# UV_MONITOR_V2_1.net
KiCad netlist of a schematic drawn in EAGLE
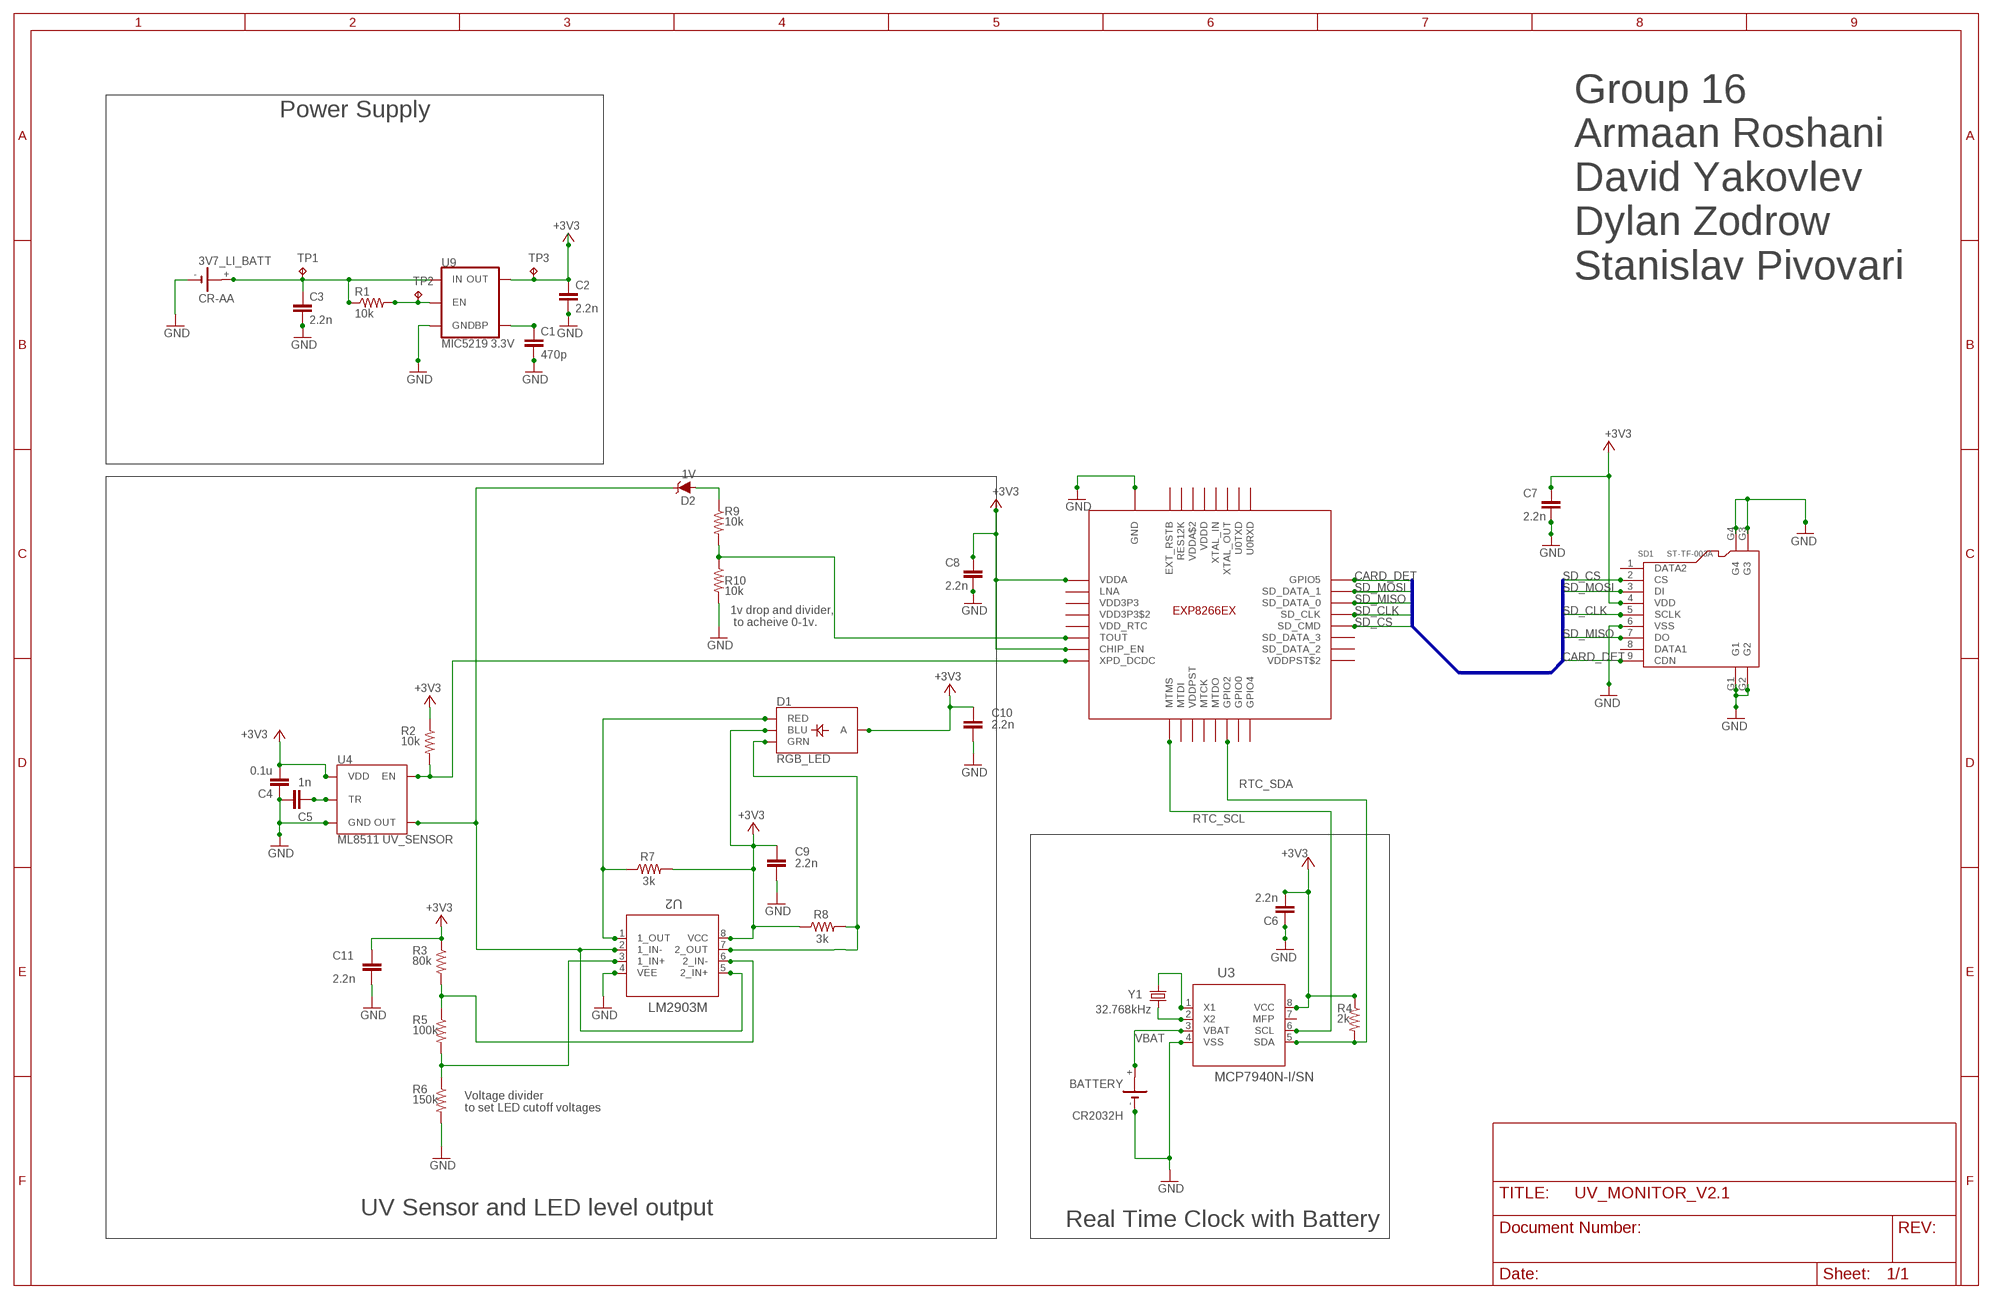
[diagram p0: schematic, sheet 1]

(export (version "E")
  (design (tool "Eeschema 10.0.6"))
  (components
    (comp (ref "3V7_LI_BATT")
      (value "CR-AA")
      (footprint "eagle-import:CRAA")
      (libsource (lib "eagle-import") (part "CR-AA"))
    )
    (comp (ref "BATTERY")
      (value "CR2032H")
      (footprint "eagle-import:CR2032H")
      (libsource (lib "eagle-import") (part "CR2032H"))
    )
    (comp (ref "C1")
      (value "470p")
      (footprint "eagle-import:C0805")
      (libsource (lib "eagle-import") (part "C-EUC0805"))
    )
    (comp (ref "C2")
      (value "2.2n")
      (footprint "eagle-import:C0805")
      (libsource (lib "eagle-import") (part "C-EUC0805"))
    )
    (comp (ref "C3")
      (value "2.2n")
      (footprint "eagle-import:C0805")
      (libsource (lib "eagle-import") (part "C-EUC0805"))
    )
    (comp (ref "C4")
      (value "0.1u")
      (footprint "eagle-import:C0805")
      (libsource (lib "eagle-import") (part "C-EUC0805"))
    )
    (comp (ref "C5")
      (value "1n")
      (footprint "eagle-import:C0805")
      (libsource (lib "eagle-import") (part "C-EUC0805"))
    )
    (comp (ref "C6")
      (value "2.2n")
      (footprint "eagle-import:C0805")
      (libsource (lib "eagle-import") (part "C-EUC0805"))
    )
    (comp (ref "C7")
      (value "2.2n")
      (footprint "eagle-import:C0805")
      (libsource (lib "eagle-import") (part "C-EUC0805"))
    )
    (comp (ref "C8")
      (value "2.2n")
      (footprint "eagle-import:C0805")
      (libsource (lib "eagle-import") (part "C-EUC0805"))
    )
    (comp (ref "C9")
      (value "2.2n")
      (footprint "eagle-import:C0805")
      (libsource (lib "eagle-import") (part "C-EUC0805"))
    )
    (comp (ref "C10")
      (value "2.2n")
      (footprint "eagle-import:C0805")
      (libsource (lib "eagle-import") (part "C-EUC0805"))
    )
    (comp (ref "C11")
      (value "2.2n")
      (footprint "eagle-import:C0805")
      (libsource (lib "eagle-import") (part "C-EUC0805"))
    )
    (comp (ref "D1")
      (value "RGB_LED")
      (footprint "eagle-import:LED-TRICOLOR-SMD")
      (libsource (lib "eagle-import") (part "LED-RGB-CASMD"))
    )
    (comp (ref "D2")
      (value "1V")
      (footprint "eagle-import:SOD-323")
      (libsource (lib "eagle-import") (part "DIODE-ZENER-BZT52C3V6S"))
    )
    (comp (ref "R1")
      (value "10k")
      (footprint "eagle-import:R0805")
      (libsource (lib "eagle-import") (part "R-US_R0805"))
    )
    (comp (ref "R2")
      (value "10k")
      (footprint "eagle-import:R0805")
      (libsource (lib "eagle-import") (part "R-US_R0805"))
    )
    (comp (ref "R3")
      (value "80k")
      (footprint "eagle-import:R0805")
      (libsource (lib "eagle-import") (part "R-US_R0805"))
    )
    (comp (ref "R4")
      (value "2k")
      (footprint "eagle-import:R0805")
      (libsource (lib "eagle-import") (part "R-US_R0805"))
    )
    (comp (ref "R5")
      (value "100k")
      (footprint "eagle-import:R0805")
      (libsource (lib "eagle-import") (part "R-US_R0805"))
    )
    (comp (ref "R6")
      (value "150k")
      (footprint "eagle-import:R0805")
      (libsource (lib "eagle-import") (part "R-US_R0805"))
    )
    (comp (ref "R7")
      (value "3k")
      (footprint "eagle-import:R0805")
      (libsource (lib "eagle-import") (part "R-US_R0805"))
    )
    (comp (ref "R8")
      (value "3k")
      (footprint "eagle-import:R0805")
      (libsource (lib "eagle-import") (part "R-US_R0805"))
    )
    (comp (ref "R9")
      (value "10k")
      (footprint "eagle-import:R0805")
      (libsource (lib "eagle-import") (part "R-US_R0805"))
    )
    (comp (ref "R10")
      (value "10k")
      (footprint "eagle-import:R0805")
      (libsource (lib "eagle-import") (part "R-US_R0805"))
    )
    (comp (ref "SD1")
      (value "ST-TF-003A")
      (footprint "eagle-import:MICRO-SD9+4P-SMD-16.1X14.5X1.85MM")
      (libsource (lib "eagle-import") (part "MICRO-SD-CARD-SOCKET-9P(ST-TF-003A)"))
    )
    (comp (ref "TP1")
      (value "TPPAD1-13")
      (footprint "eagle-import:P1-13")
      (libsource (lib "eagle-import") (part "TPPAD1-13"))
    )
    (comp (ref "TP2")
      (value "TPPAD1-13")
      (footprint "eagle-import:P1-13")
      (libsource (lib "eagle-import") (part "TPPAD1-13"))
    )
    (comp (ref "TP3")
      (value "TPPAD1-13")
      (footprint "eagle-import:P1-13")
      (libsource (lib "eagle-import") (part "TPPAD1-13"))
    )
    (comp (ref "U1")
      (value "ESP8266EX")
      (footprint "eagle-import:ESP8266EX")
      (libsource (lib "eagle-import") (part "ESP8266EX"))
    )
    (comp (ref "U2")
      (value "LM2903M")
      (footprint "eagle-import:M08A")
      (libsource (lib "eagle-import") (part "LM2903M"))
    )
    (comp (ref "U3")
      (value "MCP7940N-I/SN")
      (footprint "eagle-import:SOIC8-N_MC")
      (fields (field (name "MANUFACTURER_PART_NUMBER") "MCP7940NISN"))
      (libsource (lib "eagle-import") (part "MCP7940N-I/SN"))
    )
    (comp (ref "U4")
      (value "ML8511 UV_SENSOR")
      (footprint "eagle-import:ML8511")
      (libsource (lib "eagle-import") (part "ML8511"))
    )
    (comp (ref "U9")
      (value "MIC5219 3.3V")
      (footprint "eagle-import:SOT23-5")
      (libsource (lib "eagle-import") (part "V_REG_MIC52193.3V"))
    )
    (comp (ref "Y1")
      (value "32.768kHz")
      (footprint "eagle-import:CRYSTAL-SMD-2X6-CYL")
      (libsource (lib "eagle-import") (part "CRYSTAL-32.768KHZSMD-2X6"))
    )
  )
  (nets
    (net (code "1") (name "+3V3") (class "Default")
      (node (ref "C10") (pin "1") (pinfunction "1_1") (pintype "passive"))
      (node (ref "C11") (pin "1") (pinfunction "1_1") (pintype "passive"))
      (node (ref "C2") (pin "1") (pinfunction "1_1") (pintype "passive"))
      (node (ref "C4") (pin "2") (pinfunction "2_2") (pintype "passive"))
      (node (ref "C6") (pin "2") (pinfunction "2_2") (pintype "passive"))
      (node (ref "C7") (pin "1") (pinfunction "1_1") (pintype "passive"))
      (node (ref "C8") (pin "1") (pinfunction "1_1") (pintype "passive"))
      (node (ref "C9") (pin "1") (pinfunction "1_1") (pintype "passive"))
      (node (ref "D1") (pin "A") (pinfunction "A_A") (pintype "bidirectional"))
      (node (ref "D1") (pin "B") (pinfunction "BLU_B") (pintype "bidirectional"))
      (node (ref "R2") (pin "1") (pinfunction "1_1") (pintype "passive"))
      (node (ref "R3") (pin "1") (pinfunction "1_1") (pintype "passive"))
      (node (ref "R4") (pin "1") (pinfunction "1_1") (pintype "passive"))
      (node (ref "R7") (pin "2") (pinfunction "2_2") (pintype "passive"))
      (node (ref "R8") (pin "1") (pinfunction "1_1") (pintype "passive"))
      (node (ref "SD1") (pin "4") (pinfunction "VDD_4") (pintype "bidirectional"))
      (node (ref "TP3") (pin "TP") (pinfunction "TP_TP") (pintype "input"))
      (node (ref "U1") (pin "CHIP_EN") (pinfunction "CHIP_EN_CHIP_EN") (pintype "bidirectional"))
      (node (ref "U1") (pin "VDDA") (pinfunction "VDDA_VDDA") (pintype "bidirectional"))
      (node (ref "U2") (pin "8") (pinfunction "VCC_8") (pintype "passive"))
      (node (ref "U3") (pin "8") (pinfunction "VCC_8") (pintype "power_in"))
      (node (ref "U4") (pin "7") (pinfunction "VDD_7") (pintype "power_in"))
      (node (ref "U9") (pin "5") (pinfunction "OUT_5") (pintype "passive"))
    )
    (net (code "2") (name "/CARD_DET") (class "Default")
      (node (ref "SD1") (pin "9") (pinfunction "CDN_9") (pintype "bidirectional"))
      (node (ref "U1") (pin "GPOIO5") (pinfunction "GPIO5_GPOIO5") (pintype "bidirectional"))
    )
    (net (code "3") (name "/RTC_SCL") (class "Default")
      (node (ref "U1") (pin "MTMS") (pinfunction "MTMS_MTMS") (pintype "bidirectional"))
      (node (ref "U3") (pin "6") (pinfunction "SCL_6") (pintype "passive"))
    )
    (net (code "4") (name "/RTC_SDA") (class "Default")
      (node (ref "R4") (pin "2") (pinfunction "2_2") (pintype "passive"))
      (node (ref "U1") (pin "GPIO2") (pinfunction "GPIO2_GPIO2") (pintype "bidirectional"))
      (node (ref "U3") (pin "5") (pinfunction "SDA_5") (pintype "bidirectional"))
    )
    (net (code "5") (name "/SD_CLK") (class "Default")
      (node (ref "SD1") (pin "5") (pinfunction "SCLK_5") (pintype "bidirectional"))
      (node (ref "U1") (pin "SD_CLK") (pinfunction "SD_CLK_SD_CLK") (pintype "bidirectional"))
    )
    (net (code "6") (name "/SD_CS") (class "Default")
      (node (ref "SD1") (pin "2") (pinfunction "CS_2") (pintype "bidirectional"))
      (node (ref "U1") (pin "SD_CMD") (pinfunction "SD_CMD_SD_CMD") (pintype "bidirectional"))
    )
    (net (code "7") (name "/SD_MISO") (class "Default")
      (node (ref "SD1") (pin "7") (pinfunction "DO_7") (pintype "bidirectional"))
      (node (ref "U1") (pin "SD_DATA_0") (pinfunction "SD_DATA_0_SD_DATA_0") (pintype "bidirectional"))
    )
    (net (code "8") (name "/SD_MOSI") (class "Default")
      (node (ref "SD1") (pin "3") (pinfunction "DI_3") (pintype "bidirectional"))
      (node (ref "U1") (pin "SD_DATA_1") (pinfunction "SD_DATA_1_SD_DATA_1") (pintype "bidirectional"))
    )
    (net (code "9") (name "/VBAT") (class "Default")
      (node (ref "BATTERY") (pin "+") (pinfunction "+_+") (pintype "passive"))
      (node (ref "U3") (pin "3") (pinfunction "VBAT_3") (pintype "power_in"))
    )
    (net (code "10") (name "GND") (class "Default")
      (node (ref "3V7_LI_BATT") (pin "-") (pinfunction "-_-") (pintype "passive"))
      (node (ref "BATTERY") (pin "-") (pinfunction "-_-") (pintype "passive"))
      (node (ref "C1") (pin "2") (pinfunction "2_2") (pintype "passive"))
      (node (ref "C10") (pin "2") (pinfunction "2_2") (pintype "passive"))
      (node (ref "C11") (pin "2") (pinfunction "2_2") (pintype "passive"))
      (node (ref "C2") (pin "2") (pinfunction "2_2") (pintype "passive"))
      (node (ref "C3") (pin "2") (pinfunction "2_2") (pintype "passive"))
      (node (ref "C4") (pin "1") (pinfunction "1_1") (pintype "passive"))
      (node (ref "C5") (pin "2") (pinfunction "2_2") (pintype "passive"))
      (node (ref "C6") (pin "1") (pinfunction "1_1") (pintype "passive"))
      (node (ref "C7") (pin "2") (pinfunction "2_2") (pintype "passive"))
      (node (ref "C8") (pin "2") (pinfunction "2_2") (pintype "passive"))
      (node (ref "C9") (pin "2") (pinfunction "2_2") (pintype "passive"))
      (node (ref "R10") (pin "2") (pinfunction "2_2") (pintype "passive"))
      (node (ref "R6") (pin "2") (pinfunction "2_2") (pintype "passive"))
      (node (ref "SD1") (pin "6") (pinfunction "VSS_6") (pintype "bidirectional"))
      (node (ref "SD1") (pin "G1") (pinfunction "G1_G1") (pintype "bidirectional"))
      (node (ref "SD1") (pin "G2") (pinfunction "G2_G2") (pintype "bidirectional"))
      (node (ref "SD1") (pin "G3") (pinfunction "G3_G3") (pintype "bidirectional"))
      (node (ref "SD1") (pin "G4") (pinfunction "G4_G4") (pintype "bidirectional"))
      (node (ref "U1") (pin "GND") (pinfunction "GND_GND") (pintype "bidirectional"))
      (node (ref "U2") (pin "4") (pinfunction "VEE_4") (pintype "passive"))
      (node (ref "U3") (pin "4") (pinfunction "VSS_4") (pintype "power_in"))
      (node (ref "U4") (pin "5") (pinfunction "GND_5") (pintype "power_in"))
      (node (ref "U9") (pin "2") (pinfunction "GND_2") (pintype "input"))
    )
    (net (code "11") (name "Net-(D1-GRN)") (class "Default")
      (node (ref "D1") (pin "G") (pinfunction "GRN_G") (pintype "bidirectional"))
      (node (ref "R8") (pin "2") (pinfunction "2_2") (pintype "passive"))
      (node (ref "U2") (pin "7") (pinfunction "2_OUT_7") (pintype "passive"))
    )
    (net (code "12") (name "Net-(D1-RED)") (class "Default")
      (node (ref "D1") (pin "R") (pinfunction "RED_R") (pintype "bidirectional"))
      (node (ref "R7") (pin "1") (pinfunction "1_1") (pintype "passive"))
      (node (ref "U2") (pin "1") (pinfunction "1_OUT_1") (pintype "passive"))
    )
    (net (code "13") (name "Net-(D2-PadA)") (class "Default")
      (node (ref "D2") (pin "A") (pinfunction "A_A") (pintype "passive"))
      (node (ref "R9") (pin "1") (pinfunction "1_1") (pintype "passive"))
    )
    (net (code "14") (name "Net-(R10-Pad1)") (class "Default")
      (node (ref "R10") (pin "1") (pinfunction "1_1") (pintype "passive"))
      (node (ref "R9") (pin "2") (pinfunction "2_2") (pintype "passive"))
      (node (ref "U1") (pin "TOUT") (pinfunction "TOUT_TOUT") (pintype "bidirectional"))
    )
    (net (code "15") (name "Net-(U2-1_IN+)") (class "Default")
      (node (ref "R5") (pin "2") (pinfunction "2_2") (pintype "passive"))
      (node (ref "R6") (pin "1") (pinfunction "1_1") (pintype "passive"))
      (node (ref "U2") (pin "3") (pinfunction "1_IN+_3") (pintype "passive"))
    )
    (net (code "16") (name "Net-(U2-1_IN-)") (class "Default")
      (node (ref "D2") (pin "C") (pinfunction "C_C") (pintype "passive"))
      (node (ref "U2") (pin "2") (pinfunction "1_IN-_2") (pintype "passive"))
      (node (ref "U2") (pin "5") (pinfunction "2_IN+_5") (pintype "passive"))
      (node (ref "U4") (pin "8") (pinfunction "OUT_8") (pintype "output"))
    )
    (net (code "17") (name "Net-(U2-2_IN-)") (class "Default")
      (node (ref "R3") (pin "2") (pinfunction "2_2") (pintype "passive"))
      (node (ref "R5") (pin "1") (pinfunction "1_1") (pintype "passive"))
      (node (ref "U2") (pin "6") (pinfunction "2_IN-_6") (pintype "passive"))
    )
    (net (code "18") (name "Net-(U3-X1)") (class "Default")
      (node (ref "U3") (pin "1") (pinfunction "X1_1") (pintype "input"))
      (node (ref "Y1") (pin "X1") (pinfunction "1_X1") (pintype "passive"))
    )
    (net (code "19") (name "Net-(U3-X2)") (class "Default")
      (node (ref "U3") (pin "2") (pinfunction "X2_2") (pintype "output"))
      (node (ref "Y1") (pin "X2") (pinfunction "2_X2") (pintype "passive"))
    )
    (net (code "20") (name "Net-(U4-EN)") (class "Default")
      (node (ref "R2") (pin "2") (pinfunction "2_2") (pintype "passive"))
      (node (ref "U1") (pin "XPD_DCDC") (pinfunction "XPD_DCDC_XPD_DCDC") (pintype "bidirectional"))
      (node (ref "U4") (pin "4") (pinfunction "EN_4") (pintype "input"))
    )
    (net (code "21") (name "Net-(U4-TR)") (class "Default")
      (node (ref "C5") (pin "1") (pinfunction "1_1") (pintype "passive"))
      (node (ref "U4") (pin "10") (pinfunction "TR_10") (pintype "power_in"))
    )
    (net (code "22") (name "Net-(U9-BP)") (class "Default")
      (node (ref "C1") (pin "1") (pinfunction "1_1") (pintype "passive"))
      (node (ref "U9") (pin "4") (pinfunction "BP_4") (pintype "input"))
    )
    (net (code "23") (name "Net-(U9-EN)") (class "Default")
      (node (ref "R1") (pin "2") (pinfunction "2_2") (pintype "passive"))
      (node (ref "TP2") (pin "TP") (pinfunction "TP_TP") (pintype "input"))
      (node (ref "U9") (pin "3") (pinfunction "EN_3") (pintype "input"))
    )
    (net (code "24") (name "Net-(U9-IN)") (class "Default")
      (node (ref "3V7_LI_BATT") (pin "+") (pinfunction "+_+") (pintype "passive"))
      (node (ref "C3") (pin "1") (pinfunction "1_1") (pintype "passive"))
      (node (ref "R1") (pin "1") (pinfunction "1_1") (pintype "passive"))
      (node (ref "TP1") (pin "TP") (pinfunction "TP_TP") (pintype "input"))
      (node (ref "U9") (pin "1") (pinfunction "IN_1") (pintype "input"))
    )
    (net (code "25") (name "unconnected-(3V7_LI_BATT-+-Pad+@1)") (class "Default")
      (node (ref "3V7_LI_BATT") (pin "+@1") (pinfunction "+_+@1") (pintype "passive"))
    )
    (net (code "26") (name "unconnected-(BATTERY-+-Pad+@1)") (class "Default")
      (node (ref "BATTERY") (pin "+@1") (pinfunction "+_+@1") (pintype "passive"))
    )
    (net (code "27") (name "unconnected-(SD1-DATA1-Pad8)") (class "Default")
      (node (ref "SD1") (pin "8") (pinfunction "DATA1_8") (pintype "bidirectional"))
    )
    (net (code "28") (name "unconnected-(SD1-DATA2-Pad1)") (class "Default")
      (node (ref "SD1") (pin "1") (pinfunction "DATA2_1") (pintype "bidirectional"))
    )
    (net (code "29") (name "unconnected-(U1-PadEXT_RSTB)") (class "Default")
      (node (ref "U1") (pin "EXT_RSTB") (pinfunction "EXT_RSTB_EXT_RSTB") (pintype "bidirectional"))
    )
    (net (code "30") (name "unconnected-(U1-PadGPIO0)") (class "Default")
      (node (ref "U1") (pin "GPIO0") (pinfunction "GPIO0_GPIO0") (pintype "bidirectional"))
    )
    (net (code "31") (name "unconnected-(U1-PadGPIO4)") (class "Default")
      (node (ref "U1") (pin "GPIO4") (pinfunction "GPIO4_GPIO4") (pintype "bidirectional"))
    )
    (net (code "32") (name "unconnected-(U1-PadLNA)") (class "Default")
      (node (ref "U1") (pin "LNA") (pinfunction "LNA_LNA") (pintype "bidirectional"))
    )
    (net (code "33") (name "unconnected-(U1-PadMTCK)") (class "Default")
      (node (ref "U1") (pin "MTCK") (pinfunction "MTCK_MTCK") (pintype "bidirectional"))
    )
    (net (code "34") (name "unconnected-(U1-PadMTDI)") (class "Default")
      (node (ref "U1") (pin "MTDI") (pinfunction "MTDI_MTDI") (pintype "bidirectional"))
    )
    (net (code "35") (name "unconnected-(U1-PadMTDO)") (class "Default")
      (node (ref "U1") (pin "MTDO") (pinfunction "MTDO_MTDO") (pintype "bidirectional"))
    )
    (net (code "36") (name "unconnected-(U1-PadRES12K)") (class "Default")
      (node (ref "U1") (pin "RES12K") (pinfunction "RES12K_RES12K") (pintype "bidirectional"))
    )
    (net (code "37") (name "unconnected-(U1-PadSD_DATA_2)") (class "Default")
      (node (ref "U1") (pin "SD_DATA_2") (pinfunction "SD_DATA_2_SD_DATA_2") (pintype "bidirectional"))
    )
    (net (code "38") (name "unconnected-(U1-PadSD_DATA_3)") (class "Default")
      (node (ref "U1") (pin "SD_DATA_3") (pinfunction "SD_DATA_3_SD_DATA_3") (pintype "bidirectional"))
    )
    (net (code "39") (name "unconnected-(U1-PadU0RXD)") (class "Default")
      (node (ref "U1") (pin "U0RXD") (pinfunction "U0RXD_U0RXD") (pintype "bidirectional"))
    )
    (net (code "40") (name "unconnected-(U1-PadU0TXD)") (class "Default")
      (node (ref "U1") (pin "U0TXD") (pinfunction "U0TXD_U0TXD") (pintype "bidirectional"))
    )
    (net (code "41") (name "unconnected-(U1-PadVDD3P3$2)") (class "Default")
      (node (ref "U1") (pin "VDD3P3$2") (pinfunction "VDD3P3$2_VDD3P3$2") (pintype "bidirectional"))
    )
    (net (code "42") (name "unconnected-(U1-PadVDD3P3)") (class "Default")
      (node (ref "U1") (pin "VDD3P3") (pinfunction "VDD3P3_VDD3P3") (pintype "bidirectional"))
    )
    (net (code "43") (name "unconnected-(U1-PadVDDA$2)") (class "Default")
      (node (ref "U1") (pin "VDDA$2") (pinfunction "VDDA$2_VDDA$2") (pintype "bidirectional"))
    )
    (net (code "44") (name "unconnected-(U1-PadVDDD)") (class "Default")
      (node (ref "U1") (pin "VDDD") (pinfunction "VDDD_VDDD") (pintype "bidirectional"))
    )
    (net (code "45") (name "unconnected-(U1-PadVDDPST$2)") (class "Default")
      (node (ref "U1") (pin "VDDPST$2") (pinfunction "VDDPST$2_VDDPST$2") (pintype "bidirectional"))
    )
    (net (code "46") (name "unconnected-(U1-PadVDDPST)") (class "Default")
      (node (ref "U1") (pin "VDDPST") (pinfunction "VDDPST_VDDPST") (pintype "bidirectional"))
    )
    (net (code "47") (name "unconnected-(U1-PadVDD_RTC)") (class "Default")
      (node (ref "U1") (pin "VDD_RTC") (pinfunction "VDD_RTC_VDD_RTC") (pintype "bidirectional"))
    )
    (net (code "48") (name "unconnected-(U1-PadXTAL_IN)") (class "Default")
      (node (ref "U1") (pin "XTAL_IN") (pinfunction "XTAL_IN_XTAL_IN") (pintype "bidirectional"))
    )
    (net (code "49") (name "unconnected-(U1-PadXTAL_OUT)") (class "Default")
      (node (ref "U1") (pin "XTAL_OUT") (pinfunction "XTAL_OUT_XTAL_OUT") (pintype "bidirectional"))
    )
    (net (code "50") (name "unconnected-(U3-MFP-Pad7)") (class "Default")
      (node (ref "U3") (pin "7") (pinfunction "MFP_7") (pintype "passive"))
    )
  )
)
